# juggling_ballsch_2.net
KiCad netlist of a schematic drawn in EAGLE
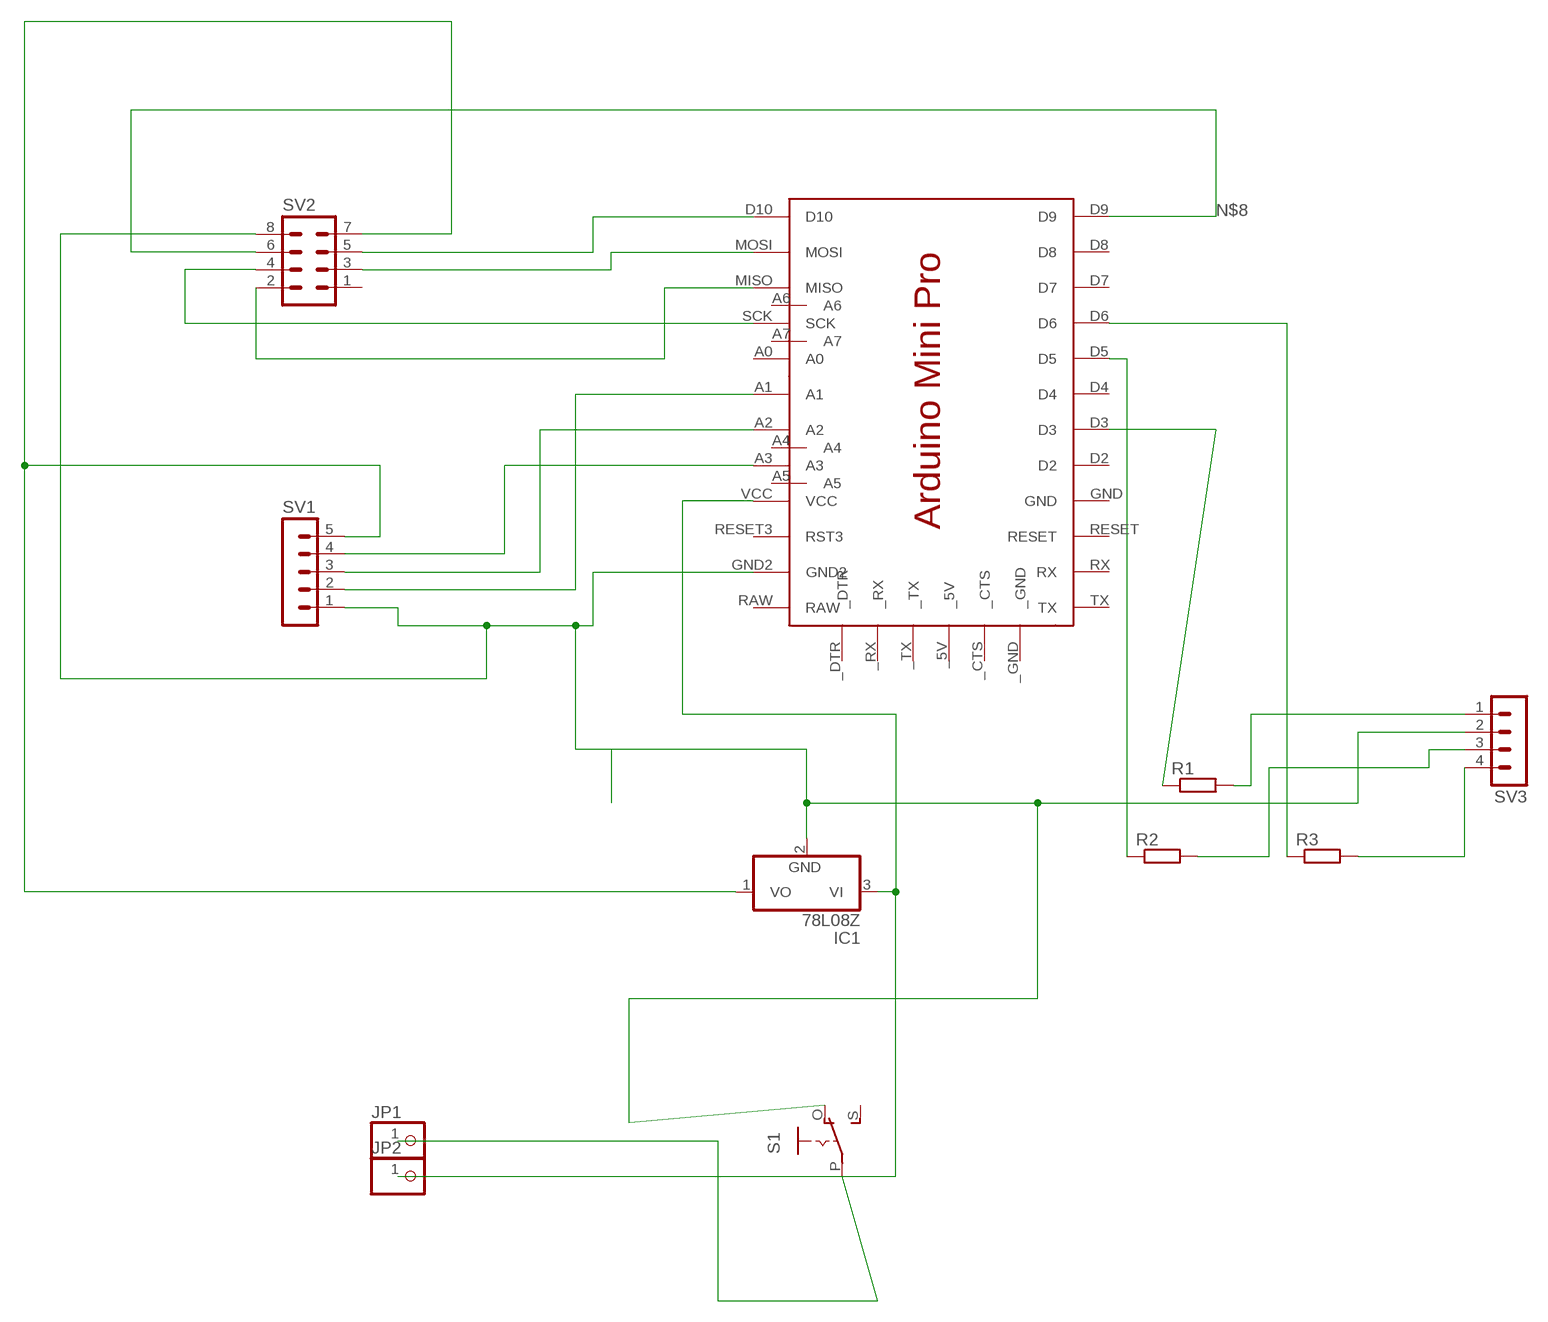
[diagram p0: schematic, sheet 1]

(export (version "E")
  (design (tool "Eeschema 10.0.6"))
  (components
    (comp (ref "IC1")
      (value "78L08Z")
      (footprint "eagle-import:TO92")
      (libsource (lib "eagle-import") (part "78ZL08"))
    )
    (comp (ref "JP1")
      (value "PINHD-1X1")
      (footprint "eagle-import:1X01")
      (libsource (lib "eagle-import") (part "PINHD-1X1"))
    )
    (comp (ref "JP2")
      (value "PINHD-1X1")
      (footprint "eagle-import:1X01")
      (libsource (lib "eagle-import") (part "PINHD-1X1"))
    )
    (comp (ref "R1")
      (value "R-EU_0207/7")
      (footprint "eagle-import:0207_7")
      (libsource (lib "eagle-import") (part "R-EU_0207/7"))
    )
    (comp (ref "R2")
      (value "R-EU_0207/7")
      (footprint "eagle-import:0207_7")
      (libsource (lib "eagle-import") (part "R-EU_0207/7"))
    )
    (comp (ref "R3")
      (value "R-EU_0207/7")
      (footprint "eagle-import:0207_7")
      (libsource (lib "eagle-import") (part "R-EU_0207/7"))
    )
    (comp (ref "S1")
      (value "EG1218S")
      (footprint "eagle-import:EG1218")
      (libsource (lib "eagle-import") (part "EG1218S"))
    )
    (comp (ref "SV1")
      (value "MA05-1")
      (footprint "eagle-import:MA05-1")
      (libsource (lib "eagle-import") (part "MA05-1"))
    )
    (comp (ref "SV2")
      (value "MA04-2")
      (footprint "eagle-import:MA04-2")
      (libsource (lib "eagle-import") (part "MA04-2"))
    )
    (comp (ref "SV3")
      (value "MA04-1")
      (footprint "eagle-import:MA04-1")
      (libsource (lib "eagle-import") (part "MA04-1"))
    )
    (comp (ref "U$1")
      (value "ARDMINIPRO")
      (footprint "eagle-import:ARDMINIPRO")
      (libsource (lib "eagle-import") (part "ARDMINIPRO"))
    )
  )
  (nets
    (net (code "1") (name "/N$8") (class "Default")
      (node (ref "SV2") (pin "6") (pinfunction "6_6") (pintype "passive"))
      (node (ref "U$1") (pin "D9") (pinfunction "D9_D9") (pintype "bidirectional"))
    )
    (net (code "2") (name "Net-(IC1-GND)") (class "Default")
      (node (ref "IC1") (pin "2") (pinfunction "GND_2") (pintype "passive"))
      (node (ref "S1") (pin "O") (pinfunction "O_O") (pintype "passive"))
      (node (ref "SV1") (pin "1") (pinfunction "1_1") (pintype "passive"))
      (node (ref "SV2") (pin "8") (pinfunction "8_8") (pintype "passive"))
      (node (ref "SV3") (pin "2") (pinfunction "2_2") (pintype "passive"))
      (node (ref "U$1") (pin "GND2") (pinfunction "GND2_GND2") (pintype "bidirectional"))
    )
    (net (code "3") (name "Net-(IC1-VI)") (class "Default")
      (node (ref "IC1") (pin "3") (pinfunction "VI_3") (pintype "input"))
      (node (ref "JP2") (pin "1") (pinfunction "1_1") (pintype "passive"))
      (node (ref "U$1") (pin "VCC") (pinfunction "VCC_VCC") (pintype "bidirectional"))
    )
    (net (code "4") (name "Net-(IC1-VO)") (class "Default")
      (node (ref "IC1") (pin "1") (pinfunction "VO_1") (pintype "passive"))
      (node (ref "SV1") (pin "5") (pinfunction "5_5") (pintype "passive"))
      (node (ref "SV2") (pin "7") (pinfunction "7_7") (pintype "passive"))
    )
    (net (code "5") (name "Net-(JP1-Pad1)") (class "Default")
      (node (ref "JP1") (pin "1") (pinfunction "1_1") (pintype "passive"))
      (node (ref "S1") (pin "P") (pinfunction "P_P") (pintype "passive"))
    )
    (net (code "6") (name "Net-(R1-Pad1)") (class "Default")
      (node (ref "R1") (pin "1") (pinfunction "1_1") (pintype "passive"))
      (node (ref "U$1") (pin "D3") (pinfunction "D3_D3") (pintype "bidirectional"))
    )
    (net (code "7") (name "Net-(R1-Pad2)") (class "Default")
      (node (ref "R1") (pin "2") (pinfunction "2_2") (pintype "passive"))
      (node (ref "SV3") (pin "1") (pinfunction "1_1") (pintype "passive"))
    )
    (net (code "8") (name "Net-(R2-Pad1)") (class "Default")
      (node (ref "R2") (pin "1") (pinfunction "1_1") (pintype "passive"))
      (node (ref "U$1") (pin "D5") (pinfunction "D5_D5") (pintype "bidirectional"))
    )
    (net (code "9") (name "Net-(R2-Pad2)") (class "Default")
      (node (ref "R2") (pin "2") (pinfunction "2_2") (pintype "passive"))
      (node (ref "SV3") (pin "3") (pinfunction "3_3") (pintype "passive"))
    )
    (net (code "10") (name "Net-(R3-Pad1)") (class "Default")
      (node (ref "R3") (pin "1") (pinfunction "1_1") (pintype "passive"))
      (node (ref "U$1") (pin "D6") (pinfunction "D6_D6") (pintype "bidirectional"))
    )
    (net (code "11") (name "Net-(R3-Pad2)") (class "Default")
      (node (ref "R3") (pin "2") (pinfunction "2_2") (pintype "passive"))
      (node (ref "SV3") (pin "4") (pinfunction "4_4") (pintype "passive"))
    )
    (net (code "12") (name "Net-(SV1-Pad2)") (class "Default")
      (node (ref "SV1") (pin "2") (pinfunction "2_2") (pintype "passive"))
      (node (ref "U$1") (pin "A1") (pinfunction "A1_A1") (pintype "bidirectional"))
    )
    (net (code "13") (name "Net-(SV1-Pad3)") (class "Default")
      (node (ref "SV1") (pin "3") (pinfunction "3_3") (pintype "passive"))
      (node (ref "U$1") (pin "A2") (pinfunction "A2_A2") (pintype "bidirectional"))
    )
    (net (code "14") (name "Net-(SV1-Pad4)") (class "Default")
      (node (ref "SV1") (pin "4") (pinfunction "4_4") (pintype "passive"))
      (node (ref "U$1") (pin "A3") (pinfunction "A3_A3") (pintype "bidirectional"))
    )
    (net (code "15") (name "Net-(SV2-Pad2)") (class "Default")
      (node (ref "SV2") (pin "2") (pinfunction "2_2") (pintype "passive"))
      (node (ref "U$1") (pin "MISO") (pinfunction "MISO_MISO") (pintype "bidirectional"))
    )
    (net (code "16") (name "Net-(SV2-Pad3)") (class "Default")
      (node (ref "SV2") (pin "3") (pinfunction "3_3") (pintype "passive"))
      (node (ref "U$1") (pin "MOSI") (pinfunction "MOSI_MOSI") (pintype "bidirectional"))
    )
    (net (code "17") (name "Net-(SV2-Pad4)") (class "Default")
      (node (ref "SV2") (pin "4") (pinfunction "4_4") (pintype "passive"))
      (node (ref "U$1") (pin "SCK") (pinfunction "SCK_SCK") (pintype "bidirectional"))
    )
    (net (code "18") (name "Net-(SV2-Pad5)") (class "Default")
      (node (ref "SV2") (pin "5") (pinfunction "5_5") (pintype "passive"))
      (node (ref "U$1") (pin "D10") (pinfunction "D10_D10") (pintype "bidirectional"))
    )
    (net (code "19") (name "unconnected-(S1-PadS)") (class "Default")
      (node (ref "S1") (pin "S") (pinfunction "S_S") (pintype "passive"))
    )
    (net (code "20") (name "unconnected-(SV2-Pad1)") (class "Default")
      (node (ref "SV2") (pin "1") (pinfunction "1_1") (pintype "passive"))
    )
    (net (code "21") (name "unconnected-(U$1-PadA0)") (class "Default")
      (node (ref "U$1") (pin "A0") (pinfunction "A0_A0") (pintype "bidirectional"))
    )
    (net (code "22") (name "unconnected-(U$1-PadA4)") (class "Default")
      (node (ref "U$1") (pin "A4") (pinfunction "A4_A4") (pintype "bidirectional"))
    )
    (net (code "23") (name "unconnected-(U$1-PadA5)") (class "Default")
      (node (ref "U$1") (pin "A5") (pinfunction "A5_A5") (pintype "bidirectional"))
    )
    (net (code "24") (name "unconnected-(U$1-PadA6)") (class "Default")
      (node (ref "U$1") (pin "A6") (pinfunction "A6_A6") (pintype "bidirectional"))
    )
    (net (code "25") (name "unconnected-(U$1-PadA7)") (class "Default")
      (node (ref "U$1") (pin "A7") (pinfunction "A7_A7") (pintype "bidirectional"))
    )
    (net (code "26") (name "unconnected-(U$1-PadD2)") (class "Default")
      (node (ref "U$1") (pin "D2") (pinfunction "D2_D2") (pintype "bidirectional"))
    )
    (net (code "27") (name "unconnected-(U$1-PadD4)") (class "Default")
      (node (ref "U$1") (pin "D4") (pinfunction "D4_D4") (pintype "bidirectional"))
    )
    (net (code "28") (name "unconnected-(U$1-PadD7)") (class "Default")
      (node (ref "U$1") (pin "D7") (pinfunction "D7_D7") (pintype "bidirectional"))
    )
    (net (code "29") (name "unconnected-(U$1-PadD8)") (class "Default")
      (node (ref "U$1") (pin "D8") (pinfunction "D8_D8") (pintype "bidirectional"))
    )
    (net (code "30") (name "unconnected-(U$1-PadGND)") (class "Default")
      (node (ref "U$1") (pin "GND") (pinfunction "GND_GND") (pintype "bidirectional"))
    )
    (net (code "31") (name "unconnected-(U$1-PadRAW)") (class "Default")
      (node (ref "U$1") (pin "RAW") (pinfunction "RAW_RAW") (pintype "bidirectional"))
    )
    (net (code "32") (name "unconnected-(U$1-PadRESET)") (class "Default")
      (node (ref "U$1") (pin "RESET") (pinfunction "RESET_RESET") (pintype "bidirectional"))
    )
    (net (code "33") (name "unconnected-(U$1-PadRX)") (class "Default")
      (node (ref "U$1") (pin "RX") (pinfunction "RX_RX") (pintype "bidirectional"))
    )
    (net (code "34") (name "unconnected-(U$1-PadTX)") (class "Default")
      (node (ref "U$1") (pin "TX") (pinfunction "TX_TX") (pintype "bidirectional"))
    )
    (net (code "35") (name "unconnected-(U$1-Pad_5V)") (class "Default")
      (node (ref "U$1") (pin "_5V") (pinfunction "_5V__5V") (pintype "bidirectional"))
    )
    (net (code "36") (name "unconnected-(U$1-Pad_CTS)") (class "Default")
      (node (ref "U$1") (pin "_CTS") (pinfunction "_CTS__CTS") (pintype "bidirectional"))
    )
    (net (code "37") (name "unconnected-(U$1-Pad_DTR)") (class "Default")
      (node (ref "U$1") (pin "_DTR") (pinfunction "_DTR__DTR") (pintype "bidirectional"))
    )
    (net (code "38") (name "unconnected-(U$1-Pad_GND)") (class "Default")
      (node (ref "U$1") (pin "_GND") (pinfunction "_GND__GND") (pintype "bidirectional"))
    )
    (net (code "39") (name "unconnected-(U$1-Pad_RX)") (class "Default")
      (node (ref "U$1") (pin "_RX") (pinfunction "_RX__RX") (pintype "bidirectional"))
    )
    (net (code "40") (name "unconnected-(U$1-Pad_TX)") (class "Default")
      (node (ref "U$1") (pin "_TX") (pinfunction "_TX__TX") (pintype "bidirectional"))
    )
    (net (code "41") (name "unconnected-(U$1-RST3-PadRESET3)") (class "Default")
      (node (ref "U$1") (pin "RESET3") (pinfunction "RST3_RESET3") (pintype "bidirectional"))
    )
  )
)
